# i2c_sensor_and_led_hat.net
KiCad netlist of a schematic drawn in EAGLE
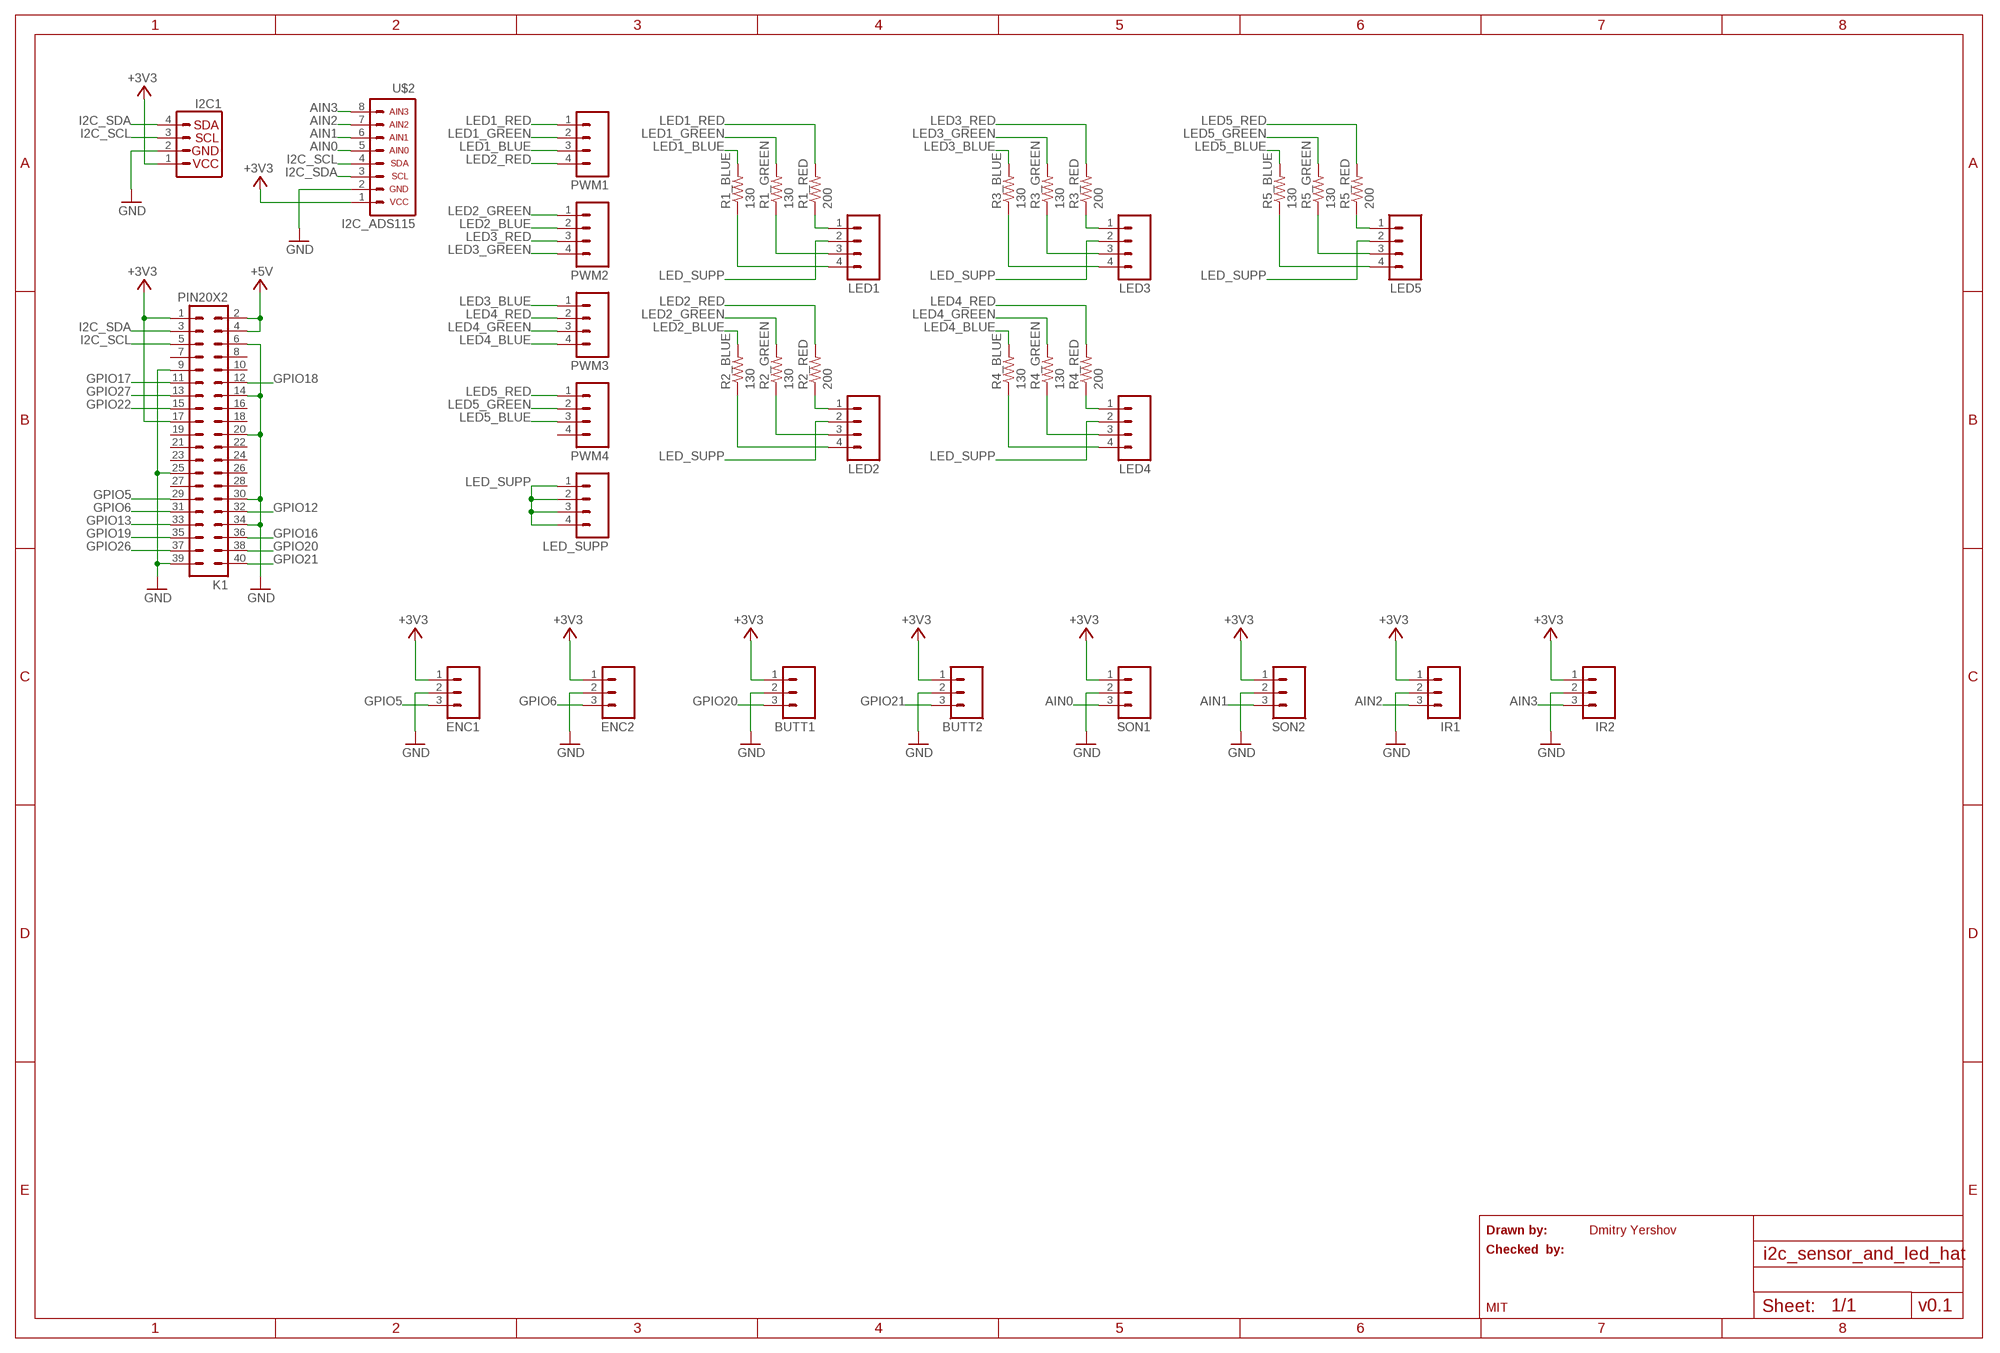
[diagram p0: schematic, sheet 1]

(export (version "E")
  (design (tool "Eeschema 10.0.6"))
  (components
    (comp (ref "BUTT1")
      (value "M03PTH")
      (footprint "eagle-import:1X03")
      (libsource (lib "eagle-import") (part "M03PTH"))
    )
    (comp (ref "BUTT2")
      (value "M03PTH")
      (footprint "eagle-import:1X03")
      (libsource (lib "eagle-import") (part "M03PTH"))
    )
    (comp (ref "ENC1")
      (value "M03PTH")
      (footprint "eagle-import:1X03")
      (libsource (lib "eagle-import") (part "M03PTH"))
    )
    (comp (ref "ENC2")
      (value "M03PTH")
      (footprint "eagle-import:1X03")
      (libsource (lib "eagle-import") (part "M03PTH"))
    )
    (comp (ref "I2C1")
      (value "I2C_IMU_L3GD20H+LSM303")
      (footprint "eagle-import:1X04")
      (libsource (lib "eagle-import") (part "I2C_IMU_L3GD20H+LSM303"))
    )
    (comp (ref "IR1")
      (value "M03PTH")
      (footprint "eagle-import:1X03")
      (libsource (lib "eagle-import") (part "M03PTH"))
    )
    (comp (ref "IR2")
      (value "M03PTH")
      (footprint "eagle-import:1X03")
      (libsource (lib "eagle-import") (part "M03PTH"))
    )
    (comp (ref "K1")
      (value "PIN20X2")
      (footprint "eagle-import:PIN_20X2")
      (libsource (lib "eagle-import") (part "PIN20X2"))
    )
    (comp (ref "LED1")
      (value "M04PTH")
      (footprint "eagle-import:1X04")
      (libsource (lib "eagle-import") (part "M04PTH"))
    )
    (comp (ref "LED2")
      (value "M04PTH")
      (footprint "eagle-import:1X04")
      (libsource (lib "eagle-import") (part "M04PTH"))
    )
    (comp (ref "LED3")
      (value "M04PTH")
      (footprint "eagle-import:1X04")
      (libsource (lib "eagle-import") (part "M04PTH"))
    )
    (comp (ref "LED4")
      (value "M04PTH")
      (footprint "eagle-import:1X04")
      (libsource (lib "eagle-import") (part "M04PTH"))
    )
    (comp (ref "LED5")
      (value "M04PTH")
      (footprint "eagle-import:1X04")
      (libsource (lib "eagle-import") (part "M04PTH"))
    )
    (comp (ref "LED_SUPP")
      (value "M041X04_NO_SILK")
      (footprint "eagle-import:1X04_NO_SILK")
      (libsource (lib "eagle-import") (part "M041X04_NO_SILK"))
    )
    (comp (ref "PWM1")
      (value "M041X04_NO_SILK")
      (footprint "eagle-import:1X04_NO_SILK")
      (libsource (lib "eagle-import") (part "M041X04_NO_SILK"))
    )
    (comp (ref "PWM2")
      (value "M041X04_NO_SILK")
      (footprint "eagle-import:1X04_NO_SILK")
      (libsource (lib "eagle-import") (part "M041X04_NO_SILK"))
    )
    (comp (ref "PWM3")
      (value "M041X04_NO_SILK")
      (footprint "eagle-import:1X04_NO_SILK")
      (libsource (lib "eagle-import") (part "M041X04_NO_SILK"))
    )
    (comp (ref "PWM4")
      (value "M041X04_NO_SILK")
      (footprint "eagle-import:1X04_NO_SILK")
      (libsource (lib "eagle-import") (part "M041X04_NO_SILK"))
    )
    (comp (ref "R1_BLUE")
      (value "130")
      (footprint "eagle-import:0207_7")
      (libsource (lib "eagle-import") (part "R-US_0207/7"))
    )
    (comp (ref "R1_GREEN")
      (value "130")
      (footprint "eagle-import:0207_7")
      (libsource (lib "eagle-import") (part "R-US_0207/7"))
    )
    (comp (ref "R1_RED")
      (value "200")
      (footprint "eagle-import:0207_7")
      (libsource (lib "eagle-import") (part "R-US_0207/7"))
    )
    (comp (ref "R2_BLUE")
      (value "130")
      (footprint "eagle-import:0207_7")
      (libsource (lib "eagle-import") (part "R-US_0207/7"))
    )
    (comp (ref "R2_GREEN")
      (value "130")
      (footprint "eagle-import:0207_7")
      (libsource (lib "eagle-import") (part "R-US_0207/7"))
    )
    (comp (ref "R2_RED")
      (value "200")
      (footprint "eagle-import:0207_7")
      (libsource (lib "eagle-import") (part "R-US_0207/7"))
    )
    (comp (ref "R3_BLUE")
      (value "130")
      (footprint "eagle-import:0207_7")
      (libsource (lib "eagle-import") (part "R-US_0207/7"))
    )
    (comp (ref "R3_GREEN")
      (value "130")
      (footprint "eagle-import:0207_7")
      (libsource (lib "eagle-import") (part "R-US_0207/7"))
    )
    (comp (ref "R3_RED")
      (value "200")
      (footprint "eagle-import:0207_7")
      (libsource (lib "eagle-import") (part "R-US_0207/7"))
    )
    (comp (ref "R4_BLUE")
      (value "130")
      (footprint "eagle-import:0207_7")
      (libsource (lib "eagle-import") (part "R-US_0207/7"))
    )
    (comp (ref "R4_GREEN")
      (value "130")
      (footprint "eagle-import:0207_7")
      (libsource (lib "eagle-import") (part "R-US_0207/7"))
    )
    (comp (ref "R4_RED")
      (value "200")
      (footprint "eagle-import:0207_7")
      (libsource (lib "eagle-import") (part "R-US_0207/7"))
    )
    (comp (ref "R5_BLUE")
      (value "130")
      (footprint "eagle-import:0207_7")
      (libsource (lib "eagle-import") (part "R-US_0207/7"))
    )
    (comp (ref "R5_GREEN")
      (value "130")
      (footprint "eagle-import:0207_7")
      (libsource (lib "eagle-import") (part "R-US_0207/7"))
    )
    (comp (ref "R5_RED")
      (value "200")
      (footprint "eagle-import:0207_7")
      (libsource (lib "eagle-import") (part "R-US_0207/7"))
    )
    (comp (ref "SON1")
      (value "M03PTH")
      (footprint "eagle-import:1X03")
      (libsource (lib "eagle-import") (part "M03PTH"))
    )
    (comp (ref "SON2")
      (value "M03PTH")
      (footprint "eagle-import:1X03")
      (libsource (lib "eagle-import") (part "M03PTH"))
    )
    (comp (ref "U$2")
      (value "I2C_ADS115")
      (footprint "eagle-import:I2C_AX4")
      (libsource (lib "eagle-import") (part "I2C_ADS115"))
    )
  )
  (nets
    (net (code "1") (name "+3V3") (class "Default")
      (node (ref "BUTT1") (pin "1") (pinfunction "1_1") (pintype "passive"))
      (node (ref "BUTT2") (pin "1") (pinfunction "1_1") (pintype "passive"))
      (node (ref "ENC1") (pin "1") (pinfunction "1_1") (pintype "passive"))
      (node (ref "ENC2") (pin "1") (pinfunction "1_1") (pintype "passive"))
      (node (ref "I2C1") (pin "1") (pinfunction "1_1") (pintype "passive"))
      (node (ref "IR1") (pin "1") (pinfunction "1_1") (pintype "passive"))
      (node (ref "IR2") (pin "1") (pinfunction "1_1") (pintype "passive"))
      (node (ref "K1") (pin "1") (pinfunction "1_1") (pintype "passive"))
      (node (ref "K1") (pin "17") (pinfunction "17_17") (pintype "passive"))
      (node (ref "SON1") (pin "1") (pinfunction "1_1") (pintype "passive"))
      (node (ref "SON2") (pin "1") (pinfunction "1_1") (pintype "passive"))
      (node (ref "U$2") (pin "1") (pinfunction "1_1") (pintype "passive"))
    )
    (net (code "2") (name "+5V") (class "Default")
      (node (ref "K1") (pin "2") (pinfunction "2_2") (pintype "passive"))
      (node (ref "K1") (pin "4") (pinfunction "4_4") (pintype "passive"))
    )
    (net (code "3") (name "/AIN0") (class "Default")
      (node (ref "SON1") (pin "3") (pinfunction "3_3") (pintype "passive"))
      (node (ref "U$2") (pin "5") (pinfunction "5_5") (pintype "passive"))
    )
    (net (code "4") (name "/AIN1") (class "Default")
      (node (ref "SON2") (pin "3") (pinfunction "3_3") (pintype "passive"))
      (node (ref "U$2") (pin "6") (pinfunction "6_6") (pintype "passive"))
    )
    (net (code "5") (name "/AIN2") (class "Default")
      (node (ref "IR1") (pin "3") (pinfunction "3_3") (pintype "passive"))
      (node (ref "U$2") (pin "7") (pinfunction "7_7") (pintype "passive"))
    )
    (net (code "6") (name "/AIN3") (class "Default")
      (node (ref "IR2") (pin "3") (pinfunction "3_3") (pintype "passive"))
      (node (ref "U$2") (pin "8") (pinfunction "8_8") (pintype "passive"))
    )
    (net (code "7") (name "/GPIO5") (class "Default")
      (node (ref "ENC1") (pin "3") (pinfunction "3_3") (pintype "passive"))
      (node (ref "K1") (pin "29") (pinfunction "29_29") (pintype "passive"))
    )
    (net (code "8") (name "/GPIO6") (class "Default")
      (node (ref "ENC2") (pin "3") (pinfunction "3_3") (pintype "passive"))
      (node (ref "K1") (pin "31") (pinfunction "31_31") (pintype "passive"))
    )
    (net (code "9") (name "/GPIO12") (class "Default")
      (node (ref "K1") (pin "32") (pinfunction "32_32") (pintype "passive"))
    )
    (net (code "10") (name "/GPIO13") (class "Default")
      (node (ref "K1") (pin "33") (pinfunction "33_33") (pintype "passive"))
    )
    (net (code "11") (name "/GPIO16") (class "Default")
      (node (ref "K1") (pin "36") (pinfunction "36_36") (pintype "passive"))
    )
    (net (code "12") (name "/GPIO17") (class "Default")
      (node (ref "K1") (pin "11") (pinfunction "11_11") (pintype "passive"))
    )
    (net (code "13") (name "/GPIO18") (class "Default")
      (node (ref "K1") (pin "12") (pinfunction "12_12") (pintype "passive"))
    )
    (net (code "14") (name "/GPIO19") (class "Default")
      (node (ref "K1") (pin "35") (pinfunction "35_35") (pintype "passive"))
    )
    (net (code "15") (name "/GPIO20") (class "Default")
      (node (ref "BUTT1") (pin "3") (pinfunction "3_3") (pintype "passive"))
      (node (ref "K1") (pin "38") (pinfunction "38_38") (pintype "passive"))
    )
    (net (code "16") (name "/GPIO21") (class "Default")
      (node (ref "BUTT2") (pin "3") (pinfunction "3_3") (pintype "passive"))
      (node (ref "K1") (pin "40") (pinfunction "40_40") (pintype "passive"))
    )
    (net (code "17") (name "/GPIO22") (class "Default")
      (node (ref "K1") (pin "15") (pinfunction "15_15") (pintype "passive"))
    )
    (net (code "18") (name "/GPIO26") (class "Default")
      (node (ref "K1") (pin "37") (pinfunction "37_37") (pintype "passive"))
    )
    (net (code "19") (name "/GPIO27") (class "Default")
      (node (ref "K1") (pin "13") (pinfunction "13_13") (pintype "passive"))
    )
    (net (code "20") (name "/I2C_SCL") (class "Default")
      (node (ref "I2C1") (pin "3") (pinfunction "3_3") (pintype "passive"))
      (node (ref "K1") (pin "5") (pinfunction "5_5") (pintype "passive"))
      (node (ref "U$2") (pin "4") (pinfunction "4_4") (pintype "passive"))
    )
    (net (code "21") (name "/I2C_SDA") (class "Default")
      (node (ref "I2C1") (pin "4") (pinfunction "4_4") (pintype "passive"))
      (node (ref "K1") (pin "3") (pinfunction "3_3") (pintype "passive"))
      (node (ref "U$2") (pin "3") (pinfunction "3_3") (pintype "passive"))
    )
    (net (code "22") (name "/LED1_BLUE") (class "Default")
      (node (ref "PWM1") (pin "3") (pinfunction "3_3") (pintype "passive"))
      (node (ref "R1_BLUE") (pin "2") (pinfunction "2_2") (pintype "passive"))
    )
    (net (code "23") (name "/LED1_GREEN") (class "Default")
      (node (ref "PWM1") (pin "2") (pinfunction "2_2") (pintype "passive"))
      (node (ref "R1_GREEN") (pin "2") (pinfunction "2_2") (pintype "passive"))
    )
    (net (code "24") (name "/LED1_RED") (class "Default")
      (node (ref "PWM1") (pin "1") (pinfunction "1_1") (pintype "passive"))
      (node (ref "R1_RED") (pin "2") (pinfunction "2_2") (pintype "passive"))
    )
    (net (code "25") (name "/LED2_BLUE") (class "Default")
      (node (ref "PWM2") (pin "2") (pinfunction "2_2") (pintype "passive"))
      (node (ref "R2_BLUE") (pin "2") (pinfunction "2_2") (pintype "passive"))
    )
    (net (code "26") (name "/LED2_GREEN") (class "Default")
      (node (ref "PWM2") (pin "1") (pinfunction "1_1") (pintype "passive"))
      (node (ref "R2_GREEN") (pin "2") (pinfunction "2_2") (pintype "passive"))
    )
    (net (code "27") (name "/LED2_RED") (class "Default")
      (node (ref "PWM1") (pin "4") (pinfunction "4_4") (pintype "passive"))
      (node (ref "R2_RED") (pin "2") (pinfunction "2_2") (pintype "passive"))
    )
    (net (code "28") (name "/LED3_BLUE") (class "Default")
      (node (ref "PWM3") (pin "1") (pinfunction "1_1") (pintype "passive"))
      (node (ref "R3_BLUE") (pin "2") (pinfunction "2_2") (pintype "passive"))
    )
    (net (code "29") (name "/LED3_GREEN") (class "Default")
      (node (ref "PWM2") (pin "4") (pinfunction "4_4") (pintype "passive"))
      (node (ref "R3_GREEN") (pin "2") (pinfunction "2_2") (pintype "passive"))
    )
    (net (code "30") (name "/LED3_RED") (class "Default")
      (node (ref "PWM2") (pin "3") (pinfunction "3_3") (pintype "passive"))
      (node (ref "R3_RED") (pin "2") (pinfunction "2_2") (pintype "passive"))
    )
    (net (code "31") (name "/LED4_BLUE") (class "Default")
      (node (ref "PWM3") (pin "4") (pinfunction "4_4") (pintype "passive"))
      (node (ref "R4_BLUE") (pin "2") (pinfunction "2_2") (pintype "passive"))
    )
    (net (code "32") (name "/LED4_GREEN") (class "Default")
      (node (ref "PWM3") (pin "3") (pinfunction "3_3") (pintype "passive"))
      (node (ref "R4_GREEN") (pin "2") (pinfunction "2_2") (pintype "passive"))
    )
    (net (code "33") (name "/LED4_RED") (class "Default")
      (node (ref "PWM3") (pin "2") (pinfunction "2_2") (pintype "passive"))
      (node (ref "R4_RED") (pin "2") (pinfunction "2_2") (pintype "passive"))
    )
    (net (code "34") (name "/LED5_BLUE") (class "Default")
      (node (ref "PWM4") (pin "3") (pinfunction "3_3") (pintype "passive"))
      (node (ref "R5_BLUE") (pin "2") (pinfunction "2_2") (pintype "passive"))
    )
    (net (code "35") (name "/LED5_GREEN") (class "Default")
      (node (ref "PWM4") (pin "2") (pinfunction "2_2") (pintype "passive"))
      (node (ref "R5_GREEN") (pin "2") (pinfunction "2_2") (pintype "passive"))
    )
    (net (code "36") (name "/LED5_RED") (class "Default")
      (node (ref "PWM4") (pin "1") (pinfunction "1_1") (pintype "passive"))
      (node (ref "R5_RED") (pin "2") (pinfunction "2_2") (pintype "passive"))
    )
    (net (code "37") (name "/LED_SUPP") (class "Default")
      (node (ref "LED1") (pin "2") (pinfunction "2_2") (pintype "passive"))
      (node (ref "LED2") (pin "2") (pinfunction "2_2") (pintype "passive"))
      (node (ref "LED3") (pin "2") (pinfunction "2_2") (pintype "passive"))
      (node (ref "LED4") (pin "2") (pinfunction "2_2") (pintype "passive"))
      (node (ref "LED5") (pin "2") (pinfunction "2_2") (pintype "passive"))
      (node (ref "LED_SUPP") (pin "1") (pinfunction "1_1") (pintype "passive"))
      (node (ref "LED_SUPP") (pin "2") (pinfunction "2_2") (pintype "passive"))
      (node (ref "LED_SUPP") (pin "3") (pinfunction "3_3") (pintype "passive"))
      (node (ref "LED_SUPP") (pin "4") (pinfunction "4_4") (pintype "passive"))
    )
    (net (code "38") (name "GND") (class "Default")
      (node (ref "BUTT1") (pin "2") (pinfunction "2_2") (pintype "passive"))
      (node (ref "BUTT2") (pin "2") (pinfunction "2_2") (pintype "passive"))
      (node (ref "ENC1") (pin "2") (pinfunction "2_2") (pintype "passive"))
      (node (ref "ENC2") (pin "2") (pinfunction "2_2") (pintype "passive"))
      (node (ref "I2C1") (pin "2") (pinfunction "2_2") (pintype "passive"))
      (node (ref "IR1") (pin "2") (pinfunction "2_2") (pintype "passive"))
      (node (ref "IR2") (pin "2") (pinfunction "2_2") (pintype "passive"))
      (node (ref "K1") (pin "14") (pinfunction "14_14") (pintype "passive"))
      (node (ref "K1") (pin "20") (pinfunction "20_20") (pintype "passive"))
      (node (ref "K1") (pin "25") (pinfunction "25_25") (pintype "passive"))
      (node (ref "K1") (pin "30") (pinfunction "30_30") (pintype "passive"))
      (node (ref "K1") (pin "34") (pinfunction "34_34") (pintype "passive"))
      (node (ref "K1") (pin "39") (pinfunction "39_39") (pintype "passive"))
      (node (ref "K1") (pin "6") (pinfunction "6_6") (pintype "passive"))
      (node (ref "K1") (pin "9") (pinfunction "9_9") (pintype "passive"))
      (node (ref "SON1") (pin "2") (pinfunction "2_2") (pintype "passive"))
      (node (ref "SON2") (pin "2") (pinfunction "2_2") (pintype "passive"))
      (node (ref "U$2") (pin "2") (pinfunction "2_2") (pintype "passive"))
    )
    (net (code "39") (name "Net-(LED1-Pad1)") (class "Default")
      (node (ref "LED1") (pin "1") (pinfunction "1_1") (pintype "passive"))
      (node (ref "R1_RED") (pin "1") (pinfunction "1_1") (pintype "passive"))
    )
    (net (code "40") (name "Net-(LED1-Pad3)") (class "Default")
      (node (ref "LED1") (pin "3") (pinfunction "3_3") (pintype "passive"))
      (node (ref "R1_GREEN") (pin "1") (pinfunction "1_1") (pintype "passive"))
    )
    (net (code "41") (name "Net-(LED1-Pad4)") (class "Default")
      (node (ref "LED1") (pin "4") (pinfunction "4_4") (pintype "passive"))
      (node (ref "R1_BLUE") (pin "1") (pinfunction "1_1") (pintype "passive"))
    )
    (net (code "42") (name "Net-(LED2-Pad1)") (class "Default")
      (node (ref "LED2") (pin "1") (pinfunction "1_1") (pintype "passive"))
      (node (ref "R2_RED") (pin "1") (pinfunction "1_1") (pintype "passive"))
    )
    (net (code "43") (name "Net-(LED2-Pad3)") (class "Default")
      (node (ref "LED2") (pin "3") (pinfunction "3_3") (pintype "passive"))
      (node (ref "R2_GREEN") (pin "1") (pinfunction "1_1") (pintype "passive"))
    )
    (net (code "44") (name "Net-(LED2-Pad4)") (class "Default")
      (node (ref "LED2") (pin "4") (pinfunction "4_4") (pintype "passive"))
      (node (ref "R2_BLUE") (pin "1") (pinfunction "1_1") (pintype "passive"))
    )
    (net (code "45") (name "Net-(LED3-Pad1)") (class "Default")
      (node (ref "LED3") (pin "1") (pinfunction "1_1") (pintype "passive"))
      (node (ref "R3_RED") (pin "1") (pinfunction "1_1") (pintype "passive"))
    )
    (net (code "46") (name "Net-(LED3-Pad3)") (class "Default")
      (node (ref "LED3") (pin "3") (pinfunction "3_3") (pintype "passive"))
      (node (ref "R3_GREEN") (pin "1") (pinfunction "1_1") (pintype "passive"))
    )
    (net (code "47") (name "Net-(LED3-Pad4)") (class "Default")
      (node (ref "LED3") (pin "4") (pinfunction "4_4") (pintype "passive"))
      (node (ref "R3_BLUE") (pin "1") (pinfunction "1_1") (pintype "passive"))
    )
    (net (code "48") (name "Net-(LED4-Pad1)") (class "Default")
      (node (ref "LED4") (pin "1") (pinfunction "1_1") (pintype "passive"))
      (node (ref "R4_RED") (pin "1") (pinfunction "1_1") (pintype "passive"))
    )
    (net (code "49") (name "Net-(LED4-Pad3)") (class "Default")
      (node (ref "LED4") (pin "3") (pinfunction "3_3") (pintype "passive"))
      (node (ref "R4_GREEN") (pin "1") (pinfunction "1_1") (pintype "passive"))
    )
    (net (code "50") (name "Net-(LED4-Pad4)") (class "Default")
      (node (ref "LED4") (pin "4") (pinfunction "4_4") (pintype "passive"))
      (node (ref "R4_BLUE") (pin "1") (pinfunction "1_1") (pintype "passive"))
    )
    (net (code "51") (name "Net-(LED5-Pad1)") (class "Default")
      (node (ref "LED5") (pin "1") (pinfunction "1_1") (pintype "passive"))
      (node (ref "R5_RED") (pin "1") (pinfunction "1_1") (pintype "passive"))
    )
    (net (code "52") (name "Net-(LED5-Pad3)") (class "Default")
      (node (ref "LED5") (pin "3") (pinfunction "3_3") (pintype "passive"))
      (node (ref "R5_GREEN") (pin "1") (pinfunction "1_1") (pintype "passive"))
    )
    (net (code "53") (name "Net-(LED5-Pad4)") (class "Default")
      (node (ref "LED5") (pin "4") (pinfunction "4_4") (pintype "passive"))
      (node (ref "R5_BLUE") (pin "1") (pinfunction "1_1") (pintype "passive"))
    )
    (net (code "54") (name "unconnected-(K1-Pad7)") (class "Default")
      (node (ref "K1") (pin "7") (pinfunction "7_7") (pintype "passive"))
    )
    (net (code "55") (name "unconnected-(K1-Pad8)") (class "Default")
      (node (ref "K1") (pin "8") (pinfunction "8_8") (pintype "passive"))
    )
    (net (code "56") (name "unconnected-(K1-Pad10)") (class "Default")
      (node (ref "K1") (pin "10") (pinfunction "10_10") (pintype "passive"))
    )
    (net (code "57") (name "unconnected-(K1-Pad16)") (class "Default")
      (node (ref "K1") (pin "16") (pinfunction "16_16") (pintype "passive"))
    )
    (net (code "58") (name "unconnected-(K1-Pad18)") (class "Default")
      (node (ref "K1") (pin "18") (pinfunction "18_18") (pintype "passive"))
    )
    (net (code "59") (name "unconnected-(K1-Pad19)") (class "Default")
      (node (ref "K1") (pin "19") (pinfunction "19_19") (pintype "passive"))
    )
    (net (code "60") (name "unconnected-(K1-Pad21)") (class "Default")
      (node (ref "K1") (pin "21") (pinfunction "21_21") (pintype "passive"))
    )
    (net (code "61") (name "unconnected-(K1-Pad22)") (class "Default")
      (node (ref "K1") (pin "22") (pinfunction "22_22") (pintype "passive"))
    )
    (net (code "62") (name "unconnected-(K1-Pad23)") (class "Default")
      (node (ref "K1") (pin "23") (pinfunction "23_23") (pintype "passive"))
    )
    (net (code "63") (name "unconnected-(K1-Pad24)") (class "Default")
      (node (ref "K1") (pin "24") (pinfunction "24_24") (pintype "passive"))
    )
    (net (code "64") (name "unconnected-(K1-Pad26)") (class "Default")
      (node (ref "K1") (pin "26") (pinfunction "26_26") (pintype "passive"))
    )
    (net (code "65") (name "unconnected-(K1-Pad27)") (class "Default")
      (node (ref "K1") (pin "27") (pinfunction "27_27") (pintype "passive"))
    )
    (net (code "66") (name "unconnected-(K1-Pad28)") (class "Default")
      (node (ref "K1") (pin "28") (pinfunction "28_28") (pintype "passive"))
    )
    (net (code "67") (name "unconnected-(PWM4-Pad4)") (class "Default")
      (node (ref "PWM4") (pin "4") (pinfunction "4_4") (pintype "passive"))
    )
  )
)
